# rev3.net
KiCad netlist of a schematic drawn in EAGLE
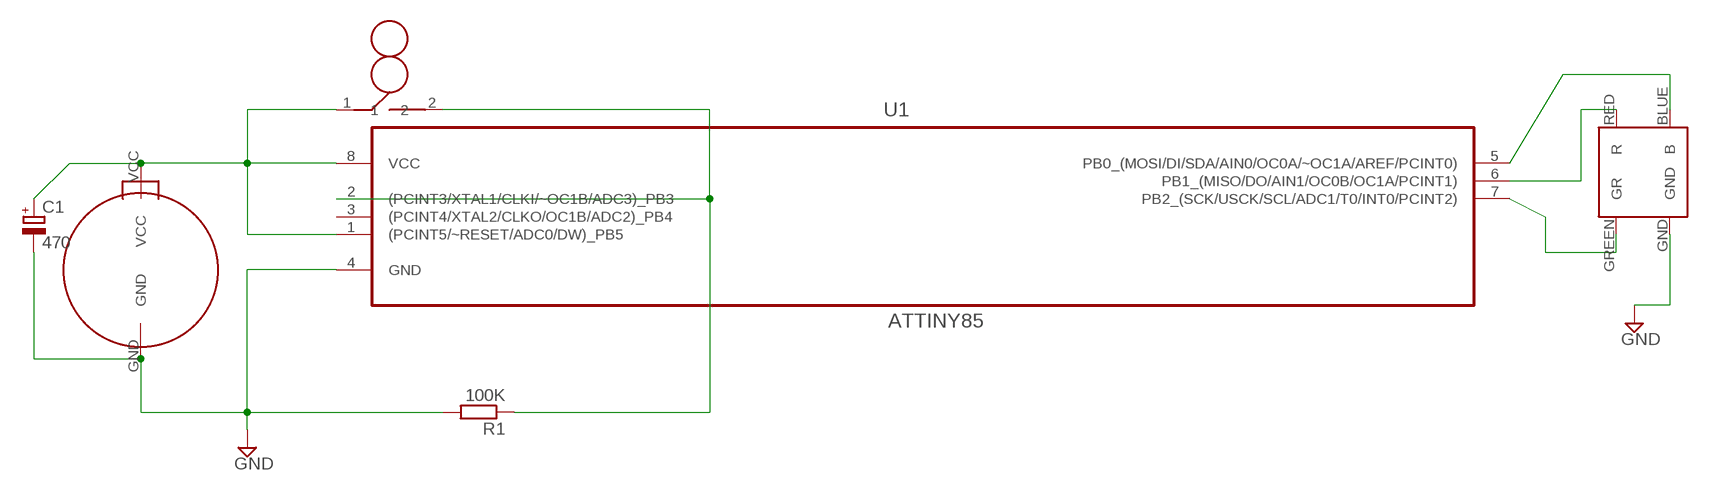
[diagram p0: schematic, sheet 1]

(export (version "E")
  (design (tool "Eeschema 10.0.6"))
  (components
    (comp (ref "C1")
      (value "470")
      (footprint "eagle-import:E2,5-6")
      (libsource (lib "eagle-import") (part "CPOL-EUE2.5-6"))
    )
    (comp (ref "R1")
      (value "100K")
      (footprint "eagle-import:0207_10")
      (libsource (lib "eagle-import") (part "R-EU_0207/10"))
    )
    (comp (ref "U$1")
      (value "CR2032_2PIN")
      (footprint "eagle-import:CR2032_2PIN")
      (libsource (lib "eagle-import") (part "CR2032_2PIN"))
    )
    (comp (ref "U$2")
      (value "RGB_4PIN")
      (footprint "eagle-import:5MM_RGB")
      (libsource (lib "eagle-import") (part "RGB_4PIN"))
    )
    (comp (ref "U$3")
      (value "BALL_SWITCH")
      (footprint "eagle-import:BALL_SW")
      (libsource (lib "eagle-import") (part "BALL_SWITCH"))
    )
    (comp (ref "U1")
      (value "ATTINY85")
      (footprint "eagle-import:DIP254P762X533-8")
      (fields (field (name "MPN") "ATTINY85-20PU") (field (name "MPN_1") "ATTINY85"))
      (libsource (lib "eagle-import") (part "ATTINY85-20PU"))
    )
  )
  (nets
    (net (code "1") (name "GND") (class "Default")
      (node (ref "C1") (pin "-") (pinfunction "-_-") (pintype "passive"))
      (node (ref "R1") (pin "2") (pinfunction "2_2") (pintype "passive"))
      (node (ref "U$1") (pin "GND") (pinfunction "GND_GND") (pintype "bidirectional"))
      (node (ref "U$2") (pin "GND") (pinfunction "GND_GND") (pintype "bidirectional"))
      (node (ref "U1") (pin "4") (pinfunction "GND_4") (pintype "passive"))
    )
    (net (code "2") (name "Net-(U$2-B)") (class "Default")
      (node (ref "U$2") (pin "BLUE") (pinfunction "B_BLUE") (pintype "bidirectional"))
      (node (ref "U1") (pin "5") (pinfunction "PB0_(MOSI/DI/SDA/AIN0/OC0A/~{OC1A/AREF/PCINT0})_5") (pintype "bidirectional"))
    )
    (net (code "3") (name "Net-(U$2-GR)") (class "Default")
      (node (ref "U$2") (pin "GREEN") (pinfunction "GR_GREEN") (pintype "bidirectional"))
      (node (ref "U1") (pin "7") (pinfunction "PB2_(SCK/USCK/SCL/ADC1/T0/INT0/PCINT2)_7") (pintype "bidirectional"))
    )
    (net (code "4") (name "Net-(U$2-R)") (class "Default")
      (node (ref "U$2") (pin "RED") (pinfunction "R_RED") (pintype "bidirectional"))
      (node (ref "U1") (pin "6") (pinfunction "PB1_(MISO/DO/AIN1/OC0B/OC1A/PCINT1)_6") (pintype "bidirectional"))
    )
    (net (code "5") (name "Net-(U1-(PCINT3{slash}XTAL1{slash}CLKI{slash}~{OC1B{slash}ADC3})_PB3)") (class "Default")
      (node (ref "R1") (pin "1") (pinfunction "1_1") (pintype "passive"))
      (node (ref "U$3") (pin "2") (pinfunction "2_2") (pintype "bidirectional"))
      (node (ref "U1") (pin "2") (pinfunction "(PCINT3/XTAL1/CLKI/~{OC1B/ADC3})_PB3_2") (pintype "bidirectional"))
    )
    (net (code "6") (name "Net-(U1-(PCINT5{slash}~{RESET{slash}ADC0{slash}DW})_PB5)") (class "Default")
      (node (ref "C1") (pin "+") (pinfunction "+_+") (pintype "passive"))
      (node (ref "U$1") (pin "VCC") (pinfunction "VCC_VCC") (pintype "bidirectional"))
      (node (ref "U$3") (pin "1") (pinfunction "1_1") (pintype "bidirectional"))
      (node (ref "U1") (pin "1") (pinfunction "(PCINT5/~{RESET/ADC0/DW})_PB5_1") (pintype "bidirectional"))
      (node (ref "U1") (pin "8") (pinfunction "VCC_8") (pintype "power_in"))
    )
    (net (code "7") (name "unconnected-(U1-(PCINT4{slash}XTAL2{slash}CLKO{slash}OC1B{slash}ADC2)_PB4-Pad3)") (class "Default")
      (node (ref "U1") (pin "3") (pinfunction "(PCINT4/XTAL2/CLKO/OC1B/ADC2)_PB4_3") (pintype "bidirectional"))
    )
  )
)
